# Output.net
KiCad netlist of a schematic drawn in Altium Designer
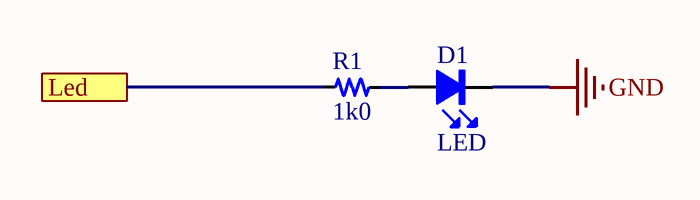
[diagram p0: Output.SchDoc]

(export (version "E")
  (design (tool "Eeschema 10.0.6"))
  (components
    (comp (ref "D1")
      (value "LED")
      (footprint "LED-0805")
      (description "LED - Light-Emitting Diode")
      (libsource (lib "RasUNMSM") (part "LED"))
    )
    (comp (ref "R1")
      (value "1k0")
      (footprint "R0805")
      (description "Single resistor")
      (fields (field (name "POWER") "0.125W"))
      (libsource (lib "RasUNMSM") (part "Resistor"))
    )
  )
  (nets
    (net (code "1") (name "/Led") (class "Default")
      (node (ref "R1") (pin "2") (pinfunction "2_2") (pintype "passive"))
    )
    (net (code "2") (name "GND") (class "Default")
      (node (ref "D1") (pin "1") (pinfunction "1_1") (pintype "passive"))
    )
    (net (code "3") (name "Net-(D1-Pad2)") (class "Default")
      (node (ref "D1") (pin "2") (pinfunction "2_2") (pintype "passive"))
      (node (ref "R1") (pin "1") (pinfunction "1_1") (pintype "passive"))
    )
  )
)
